# ledBoard.net
KiCad netlist of a schematic drawn in Altium Designer
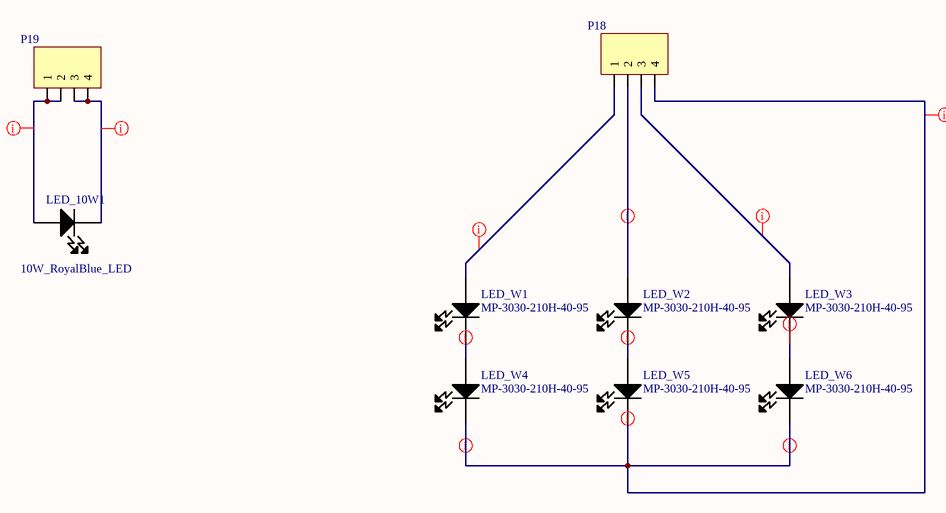
[diagram p0: ledBoard.SchDoc]

(export (version "E")
  (design (tool "Eeschema 10.0.6"))
  (components
    (comp (ref "LED_10W1")
      (value "10W_RoyalBlue_LED")
      (footprint "10W_LED_200200")
      (description "445nm LED")
      (libsource (lib "ScienceComponents") (part "10W_RoyalBlue_LED"))
    )
    (comp (ref "LED_W1")
      (value "MP-3030-210H-40-95")
      (footprint "MP-3030-210H-40-95")
      (description "White 4000K neutral 1.5W 95CRI SMT3030 LED 6V 150mA")
      (libsource (lib "ScienceComponents") (part "MP-3030-210H-40-95"))
    )
    (comp (ref "LED_W2")
      (value "MP-3030-210H-40-95")
      (footprint "MP-3030-210H-40-95")
      (description "White 4000K neutral 1.5W 95CRI SMT3030 LED 6V 150mA")
      (libsource (lib "ScienceComponents") (part "MP-3030-210H-40-95"))
    )
    (comp (ref "LED_W3")
      (value "MP-3030-210H-40-95")
      (footprint "MP-3030-210H-40-95")
      (description "White 4000K neutral 1.5W 95CRI SMT3030 LED 6V 150mA")
      (libsource (lib "ScienceComponents") (part "MP-3030-210H-40-95"))
    )
    (comp (ref "LED_W4")
      (value "MP-3030-210H-40-95")
      (footprint "MP-3030-210H-40-95")
      (description "White 4000K neutral 1.5W 95CRI SMT3030 LED 6V 150mA")
      (libsource (lib "ScienceComponents") (part "MP-3030-210H-40-95"))
    )
    (comp (ref "LED_W5")
      (value "MP-3030-210H-40-95")
      (footprint "MP-3030-210H-40-95")
      (description "White 4000K neutral 1.5W 95CRI SMT3030 LED 6V 150mA")
      (libsource (lib "ScienceComponents") (part "MP-3030-210H-40-95"))
    )
    (comp (ref "LED_W6")
      (value "MP-3030-210H-40-95")
      (footprint "MP-3030-210H-40-95")
      (description "White 4000K neutral 1.5W 95CRI SMT3030 LED 6V 150mA")
      (libsource (lib "ScienceComponents") (part "MP-3030-210H-40-95"))
    )
    (comp (ref "P18")
      (value "Mini-Fit Jr 4 Pos")
      (footprint "MOLEX 0039281043")
      (libsource (lib "RSX_Connectors") (part "Molex 0039281043"))
    )
    (comp (ref "P19")
      (value "Mini-Fit Jr 4 Pos")
      (footprint "MOLEX 0039281043")
      (libsource (lib "RSX_Connectors") (part "Molex 0039281043"))
    )
  )
  (nets
    (net (code "1") (name "Net-(LED_10W1-+)") (class "Default")
      (node (ref "LED_10W1") (pin "2") (pinfunction "+_2") (pintype "passive"))
      (node (ref "P19") (pin "1") (pinfunction "1_1") (pintype "passive"))
      (node (ref "P19") (pin "2") (pinfunction "2_2") (pintype "passive"))
    )
    (net (code "2") (name "Net-(LED_10W1--)") (class "Default")
      (node (ref "LED_10W1") (pin "1") (pinfunction "-_1") (pintype "passive"))
      (node (ref "P19") (pin "3") (pinfunction "3_3") (pintype "passive"))
      (node (ref "P19") (pin "4") (pinfunction "4_4") (pintype "passive"))
    )
    (net (code "3") (name "Net-(LED_W1-+)") (class "Default")
      (node (ref "LED_W1") (pin "2") (pinfunction "+_2") (pintype "passive"))
      (node (ref "P18") (pin "1") (pinfunction "1_1") (pintype "passive"))
    )
    (net (code "4") (name "Net-(LED_W1--)") (class "Default")
      (node (ref "LED_W1") (pin "1") (pinfunction "-_1") (pintype "passive"))
      (node (ref "LED_W4") (pin "2") (pinfunction "+_2") (pintype "passive"))
    )
    (net (code "5") (name "Net-(LED_W2-+)") (class "Default")
      (node (ref "LED_W2") (pin "2") (pinfunction "+_2") (pintype "passive"))
      (node (ref "P18") (pin "2") (pinfunction "2_2") (pintype "passive"))
    )
    (net (code "6") (name "Net-(LED_W2--)") (class "Default")
      (node (ref "LED_W2") (pin "1") (pinfunction "-_1") (pintype "passive"))
      (node (ref "LED_W5") (pin "2") (pinfunction "+_2") (pintype "passive"))
    )
    (net (code "7") (name "Net-(LED_W3-+)") (class "Default")
      (node (ref "LED_W3") (pin "2") (pinfunction "+_2") (pintype "passive"))
      (node (ref "P18") (pin "3") (pinfunction "3_3") (pintype "passive"))
    )
    (net (code "8") (name "Net-(LED_W3--)") (class "Default")
      (node (ref "LED_W3") (pin "1") (pinfunction "-_1") (pintype "passive"))
      (node (ref "LED_W6") (pin "2") (pinfunction "+_2") (pintype "passive"))
    )
    (net (code "9") (name "Net-(LED_W4--)") (class "Default")
      (node (ref "LED_W4") (pin "1") (pinfunction "-_1") (pintype "passive"))
      (node (ref "LED_W5") (pin "1") (pinfunction "-_1") (pintype "passive"))
      (node (ref "LED_W6") (pin "1") (pinfunction "-_1") (pintype "passive"))
      (node (ref "P18") (pin "4") (pinfunction "4_4") (pintype "passive"))
    )
  )
)
